# MKRWiFi1010V2_0.net
KiCad netlist of a schematic drawn in EAGLE
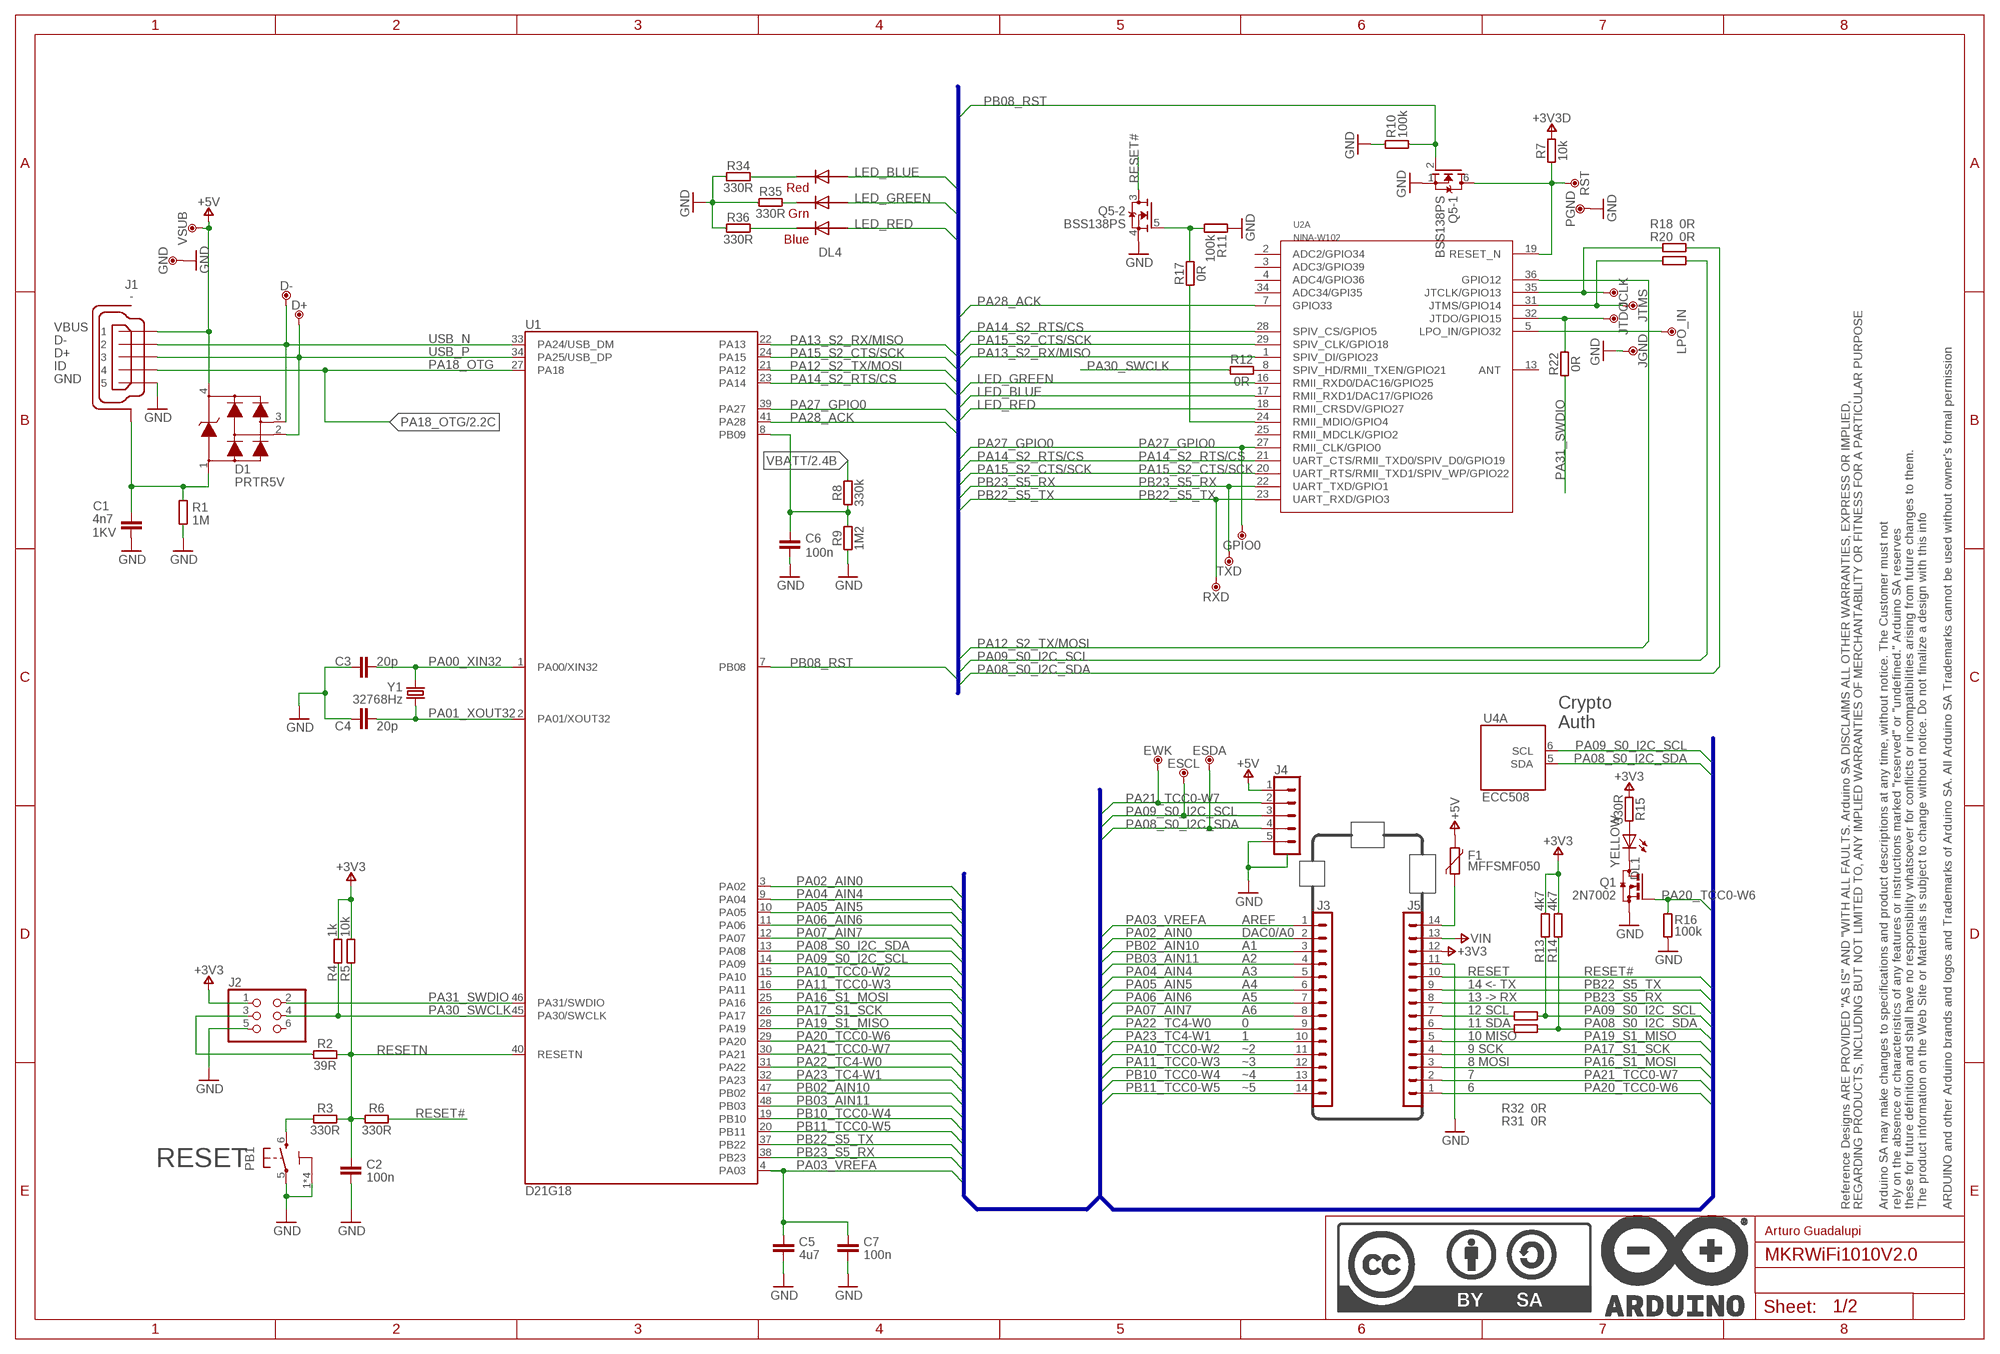
[diagram p0: schematic, sheet 1]
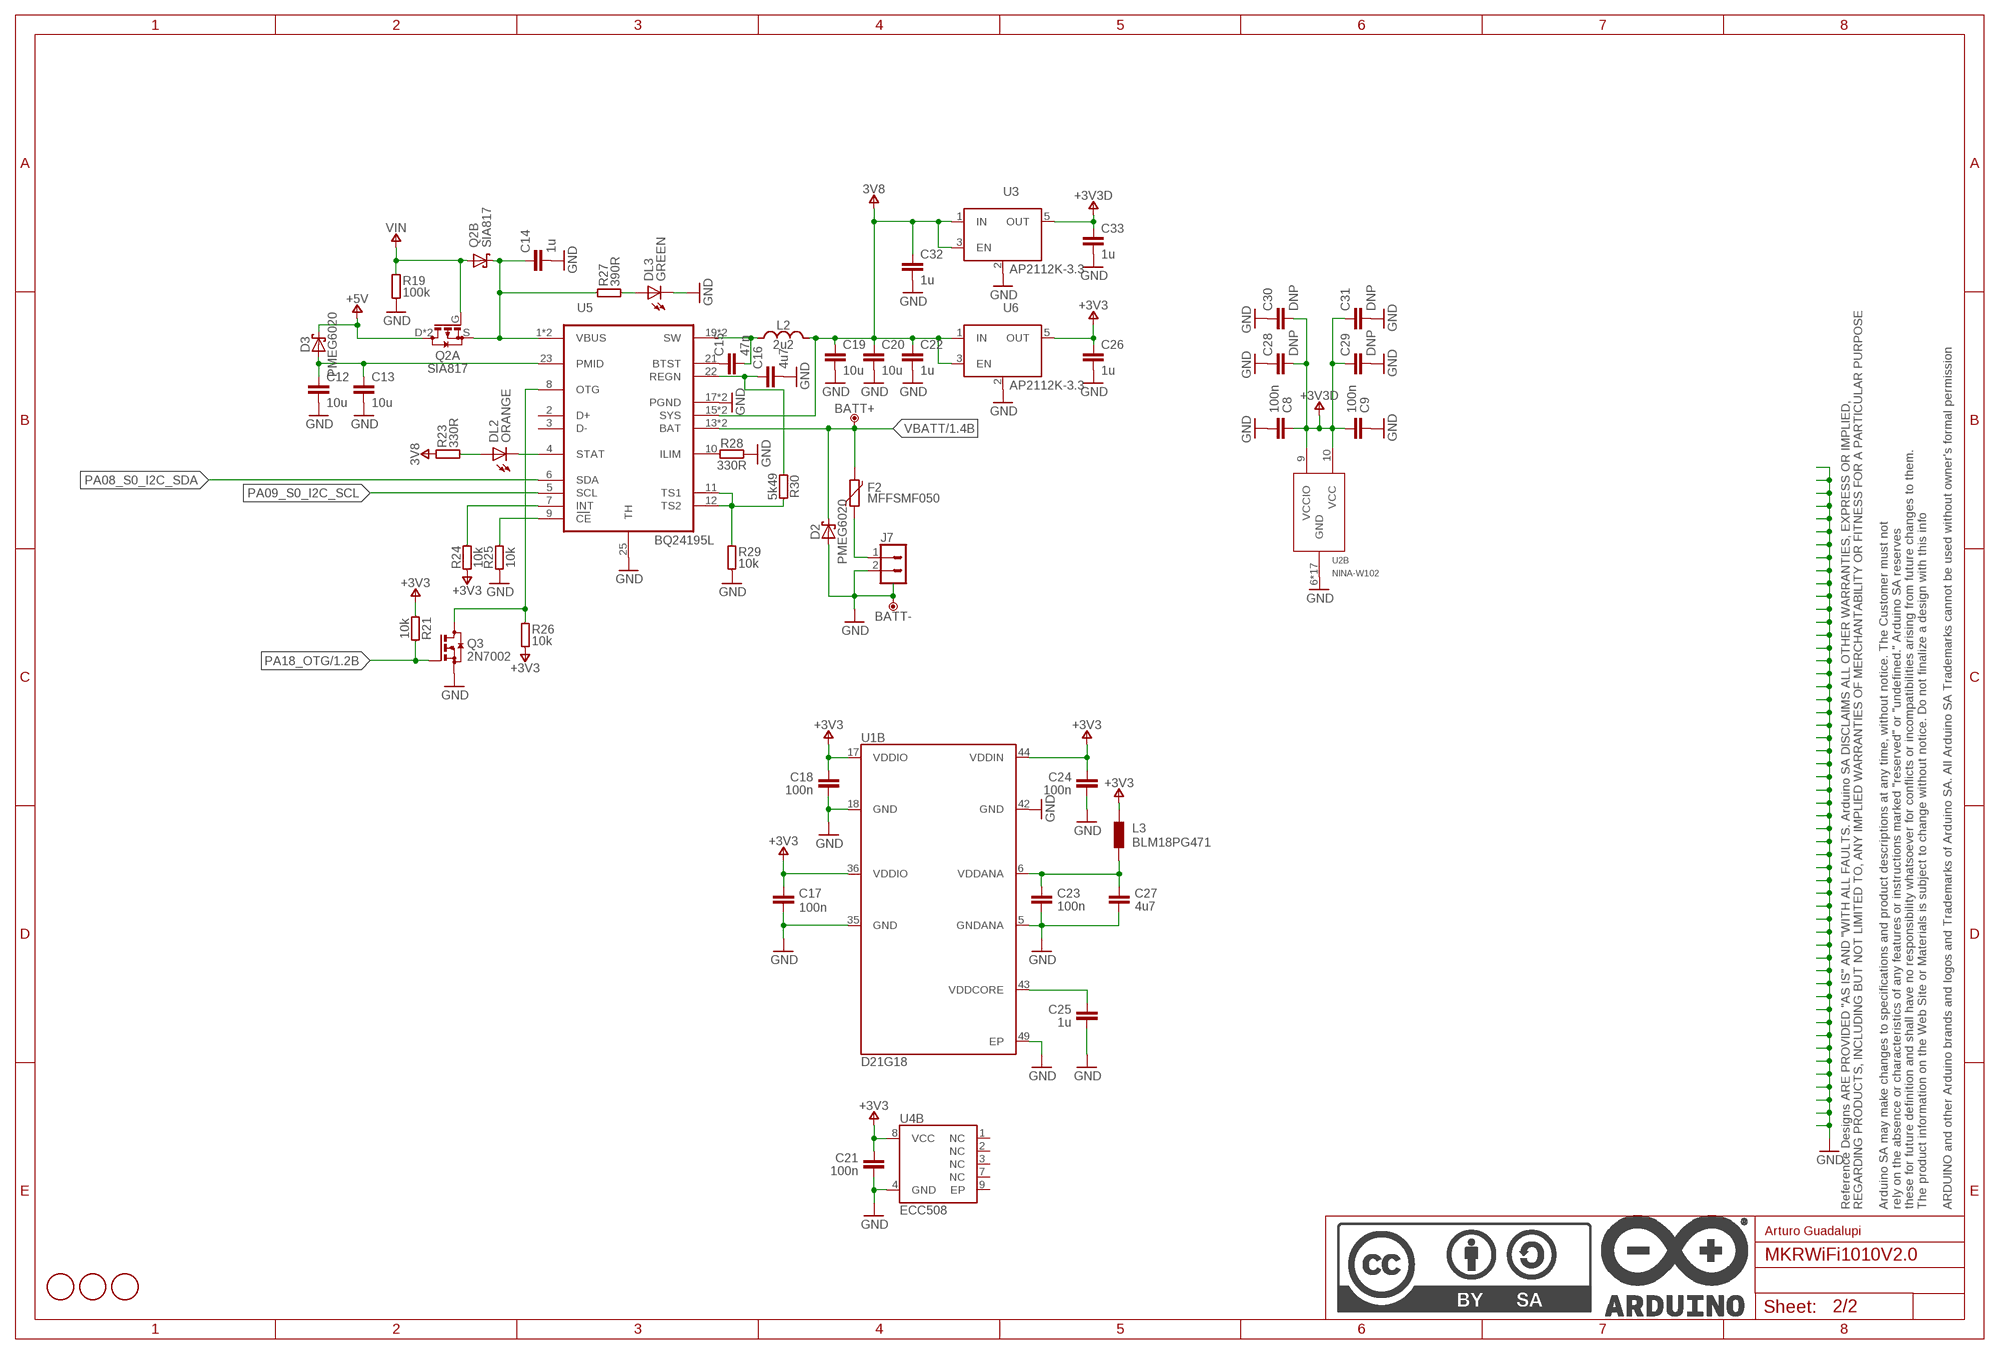
[diagram p1: schematic, sheet 2]

(export (version "E")
  (design (tool "Eeschema 10.0.6"))
  (components
    (comp (ref "C1")
      (value "4n7")
      (footprint "eagle-import:0805-R2013X50N")
      (fields (field (name "MANUFACTURER") "Kemet") (field (name "VOLTAGE") "1KV"))
      (libsource (lib "eagle-import") (part "C-08054.7NF"))
    )
    (comp (ref "C2")
      (value "100n")
      (footprint "eagle-import:0402-1005X55N")
      (fields (field (name "MANUFACTURER") "TDK"))
      (libsource (lib "eagle-import") (part "C-0402-100NF"))
    )
    (comp (ref "C3")
      (value "20p")
      (footprint "eagle-import:0402-1005X55N")
      (fields (field (name "MANUFACTURER") "Kemet"))
      (libsource (lib "eagle-import") (part "C-0402-20PF"))
    )
    (comp (ref "C4")
      (value "20p")
      (footprint "eagle-import:0402-1005X55N")
      (fields (field (name "MANUFACTURER") "Kemet"))
      (libsource (lib "eagle-import") (part "C-0402-20PF"))
    )
    (comp (ref "C5")
      (value "4u7")
      (footprint "eagle-import:0402-1005X55N")
      (fields (field (name "MANUFACTURER") "Murata"))
      (libsource (lib "eagle-import") (part "C-0402-4.7UF"))
    )
    (comp (ref "C6")
      (value "100n")
      (footprint "eagle-import:0402-1005X55N")
      (fields (field (name "MANUFACTURER") "TDK"))
      (libsource (lib "eagle-import") (part "C-0402-100NF"))
    )
    (comp (ref "C7")
      (value "100n")
      (footprint "eagle-import:0402-1005X55N")
      (fields (field (name "MANUFACTURER") "TDK"))
      (libsource (lib "eagle-import") (part "C-0402-100NF"))
    )
    (comp (ref "D+")
      (value "DNP")
      (footprint "eagle-import:TP-1.00MM")
      (libsource (lib "eagle-import") (part "TPTP-1.00MM"))
    )
    (comp (ref "D-")
      (value "DNP")
      (footprint "eagle-import:TP-1.00MM")
      (libsource (lib "eagle-import") (part "TPTP-1.00MM"))
    )
    (comp (ref "D1")
      (value "PRTR5V")
      (footprint "eagle-import:SOT190P230X110-4N")
      (fields (field (name "MANUFACTURER") "NXP"))
      (libsource (lib "eagle-import") (part "PRTR5V0U2X,215"))
    )
    (comp (ref "DL1")
      (value "YELLOW")
      (footprint "eagle-import:LEDC1608X80N-AK")
      (fields (field (name "MANUFACTURER") "Avago"))
      (libsource (lib "eagle-import") (part "LED-0603-YELLOW"))
    )
    (comp (ref "DL4")
      (value "RGB")
      (footprint "eagle-import:RGBLED")
      (fields (field (name "MANUFACTURER") "OSRAM Opto Semiconductors Inc."))
      (libsource (lib "eagle-import") (part "RGBLED5050"))
    )
    (comp (ref "ESCL")
      (value "DNP")
      (footprint "eagle-import:TP-1.00MM")
      (libsource (lib "eagle-import") (part "TPTP-1.00MM"))
    )
    (comp (ref "ESDA")
      (value "DNP")
      (footprint "eagle-import:TP-1.00MM")
      (libsource (lib "eagle-import") (part "TPTP-1.00MM"))
    )
    (comp (ref "EWK")
      (value "DNP")
      (footprint "eagle-import:TP-1.00MM")
      (libsource (lib "eagle-import") (part "TPTP-1.00MM"))
    )
    (comp (ref "F1")
      (value "MFFSMF050")
      (footprint "eagle-import:0603-1608X90N")
      (fields (field (name "MANUFACTURER") "Bourns Inc "))
      (libsource (lib "eagle-import") (part "PTC"))
    )
    (comp (ref "FRAME1")
      (value "DNP")
      (footprint "eagle-import:FRAME")
      (libsource (lib "eagle-import") (part "A3-FRAME"))
    )
    (comp (ref "GND")
      (value "DNP")
      (footprint "eagle-import:TP-1.00MM")
      (libsource (lib "eagle-import") (part "TPTP-1.00MM"))
    )
    (comp (ref "GPIO0")
      (value "DNP")
      (footprint "eagle-import:TP-0.8MM")
      (libsource (lib "eagle-import") (part "TPTP-0.8MM"))
    )
    (comp (ref "J1")
      (value "-")
      (footprint "eagle-import:ZX62-AB-5PA")
      (fields (field (name "MANUFACTURER") "Hirose"))
      (libsource (lib "eagle-import") (part "USB-MICRO"))
    )
    (comp (ref "J2")
      (value "DNP")
      (footprint "eagle-import:2X3_SMT")
      (libsource (lib "eagle-import") (part "PINHD-2X03SMD-NH-DNP"))
    )
    (comp (ref "J3")
      (value "-")
      (footprint "eagle-import:1X14_SMD_TH")
      (fields (field (name "MANUFACTURER") "ELDECO"))
      (libsource (lib "eagle-import") (part "PINHD-1X14-SMTH-SMD-MALE/FEMALE"))
    )
    (comp (ref "J4")
      (value "-")
      (footprint "eagle-import:SM05B-SRSS-TB")
      (fields (field (name "MANUFACTURER") "JST"))
      (libsource (lib "eagle-import") (part "SM05B-SRSS-TB"))
    )
    (comp (ref "J5")
      (value "-")
      (footprint "eagle-import:1X14_SMD_TH")
      (fields (field (name "MANUFACTURER") "ELDECO"))
      (libsource (lib "eagle-import") (part "PINHD-1X14-SMTH-SMD-MALE/FEMALE"))
    )
    (comp (ref "JCLK")
      (value "DNP")
      (footprint "eagle-import:TP-0.8MM")
      (libsource (lib "eagle-import") (part "TPTP-0.8MM"))
    )
    (comp (ref "JGND")
      (value "DNP")
      (footprint "eagle-import:TP-0.8MM")
      (libsource (lib "eagle-import") (part "TPTP-0.8MM"))
    )
    (comp (ref "JTDO")
      (value "DNP")
      (footprint "eagle-import:TP-0.8MM")
      (libsource (lib "eagle-import") (part "TPTP-0.8MM"))
    )
    (comp (ref "JTMS")
      (value "DNP")
      (footprint "eagle-import:TP-0.8MM")
      (libsource (lib "eagle-import") (part "TPTP-0.8MM"))
    )
    (comp (ref "LPO_IN")
      (value "DNP")
      (footprint "eagle-import:TP-1.27MM")
      (libsource (lib "eagle-import") (part "TPTP-1.27MM"))
    )
    (comp (ref "PB1")
      (value "PTS820")
      (footprint "eagle-import:C&K_PTS820_NO_HOLES")
      (fields (field (name "MANUFACTURER") "C&K"))
      (libsource (lib "eagle-import") (part "TACTILE1PTS820-NH"))
    )
    (comp (ref "PGND")
      (value "DNP")
      (footprint "eagle-import:TP-0.8MM")
      (libsource (lib "eagle-import") (part "TPTP-0.8MM"))
    )
    (comp (ref "Q1")
      (value "2N7002")
      (footprint "eagle-import:SOTFL50P160X78-3")
      (fields (field (name "MANUFACTURER") "Diodes Incorporated"))
      (libsource (lib "eagle-import") (part "2N7002T-SOT523"))
    )
    (comp (ref "Q5")
      (value "BSS138PS")
      (footprint "eagle-import:SOT363")
      (fields (field (name "MANUFACTURER") "NXP"))
      (libsource (lib "eagle-import") (part "BSS138PS"))
    )
    (comp (ref "R1")
      (value "1M")
      (footprint "eagle-import:0402-1005X55N")
      (fields (field (name "MANUFACTURER") "Yageo"))
      (libsource (lib "eagle-import") (part "R-0402-1M"))
    )
    (comp (ref "R2")
      (value "39R")
      (footprint "eagle-import:0402-1005X55N")
      (fields (field (name "MANUFACTURER") "Yageo "))
      (libsource (lib "eagle-import") (part "R-0402-39R"))
    )
    (comp (ref "R3")
      (value "330R")
      (footprint "eagle-import:0402-1005X55N")
      (fields (field (name "MANUFACTURER") "Yageo "))
      (libsource (lib "eagle-import") (part "R-0402-330R"))
    )
    (comp (ref "R4")
      (value "1k")
      (footprint "eagle-import:0402-1005X55N")
      (fields (field (name "MANUFACTURER") "Yageo"))
      (libsource (lib "eagle-import") (part "R-0402-1K"))
    )
    (comp (ref "R5")
      (value "10k")
      (footprint "eagle-import:0402-1005X55N")
      (fields (field (name "MANUFACTURER") "Yageo"))
      (libsource (lib "eagle-import") (part "R-0402-10K"))
    )
    (comp (ref "R6")
      (value "330R")
      (footprint "eagle-import:0402-1005X55N")
      (fields (field (name "MANUFACTURER") "Yageo "))
      (libsource (lib "eagle-import") (part "R-0402-330R"))
    )
    (comp (ref "R7")
      (value "10k")
      (footprint "eagle-import:0402-1005X55N")
      (fields (field (name "MANUFACTURER") "Yageo"))
      (libsource (lib "eagle-import") (part "R-0402-10K"))
    )
    (comp (ref "R8")
      (value "330k")
      (footprint "eagle-import:0402-1005X55N")
      (fields (field (name "MANUFACTURER") "Yageo"))
      (libsource (lib "eagle-import") (part "R-0402-330K"))
    )
    (comp (ref "R9")
      (value "1M2")
      (footprint "eagle-import:0402-1005X55N")
      (fields (field (name "MANUFACTURER") "Yageo"))
      (libsource (lib "eagle-import") (part "R-0402-1M2"))
    )
    (comp (ref "R10")
      (value "100k")
      (footprint "eagle-import:0402-1005X55N")
      (fields (field (name "MANUFACTURER") "Yageo "))
      (libsource (lib "eagle-import") (part "R-0402-100K"))
    )
    (comp (ref "R11")
      (value "100k")
      (footprint "eagle-import:0402-1005X55N")
      (fields (field (name "MANUFACTURER") "Yageo "))
      (libsource (lib "eagle-import") (part "R-0402-100K"))
    )
    (comp (ref "R12")
      (value "0R")
      (footprint "eagle-import:0402-1005X55N")
      (fields (field (name "MANUFACTURER") "Yageo"))
      (libsource (lib "eagle-import") (part "R-0402-0R"))
    )
    (comp (ref "R13")
      (value "4k7")
      (footprint "eagle-import:0402-1005X55N")
      (fields (field (name "MANUFACTURER") "Yageo "))
      (libsource (lib "eagle-import") (part "R-0402-4K7"))
    )
    (comp (ref "R14")
      (value "4k7")
      (footprint "eagle-import:0402-1005X55N")
      (fields (field (name "MANUFACTURER") "Yageo "))
      (libsource (lib "eagle-import") (part "R-0402-4K7"))
    )
    (comp (ref "R15")
      (value "330R")
      (footprint "eagle-import:0402-1005X55N")
      (fields (field (name "MANUFACTURER") "Yageo "))
      (libsource (lib "eagle-import") (part "R-0402-330R"))
    )
    (comp (ref "R16")
      (value "100k")
      (footprint "eagle-import:0402-1005X55N")
      (fields (field (name "MANUFACTURER") "Yageo "))
      (libsource (lib "eagle-import") (part "R-0402-100K"))
    )
    (comp (ref "R17")
      (value "0R")
      (footprint "eagle-import:0402-1005X55N")
      (fields (field (name "MANUFACTURER") "Yageo"))
      (libsource (lib "eagle-import") (part "R-0402-0R"))
    )
    (comp (ref "R18")
      (value "0R")
      (footprint "eagle-import:0402-1005X55N")
      (fields (field (name "MANUFACTURER") "Yageo"))
      (libsource (lib "eagle-import") (part "R-0402-0R"))
    )
    (comp (ref "R20")
      (value "0R")
      (footprint "eagle-import:0402-1005X55N")
      (fields (field (name "MANUFACTURER") "Yageo"))
      (libsource (lib "eagle-import") (part "R-0402-0R"))
    )
    (comp (ref "R22")
      (value "0R")
      (footprint "eagle-import:0402-1005X55N")
      (fields (field (name "MANUFACTURER") "Yageo"))
      (libsource (lib "eagle-import") (part "R-0402-0R"))
    )
    (comp (ref "R31")
      (value "0R")
      (footprint "eagle-import:0402-1005X55N")
      (fields (field (name "MANUFACTURER") "Yageo"))
      (libsource (lib "eagle-import") (part "R-0402-0R"))
    )
    (comp (ref "R32")
      (value "0R")
      (footprint "eagle-import:0402-1005X55N")
      (fields (field (name "MANUFACTURER") "Yageo"))
      (libsource (lib "eagle-import") (part "R-0402-0R"))
    )
    (comp (ref "R34")
      (value "330R")
      (footprint "eagle-import:0402-1005X55N")
      (fields (field (name "MANUFACTURER") "Yageo "))
      (libsource (lib "eagle-import") (part "R-0402-330R"))
    )
    (comp (ref "R35")
      (value "330R")
      (footprint "eagle-import:0402-1005X55N")
      (fields (field (name "MANUFACTURER") "Yageo "))
      (libsource (lib "eagle-import") (part "R-0402-330R"))
    )
    (comp (ref "R36")
      (value "330R")
      (footprint "eagle-import:0402-1005X55N")
      (fields (field (name "MANUFACTURER") "Yageo "))
      (libsource (lib "eagle-import") (part "R-0402-330R"))
    )
    (comp (ref "RST")
      (value "DNP")
      (footprint "eagle-import:TP-0.8MM")
      (libsource (lib "eagle-import") (part "TPTP-0.8MM"))
    )
    (comp (ref "RXD")
      (value "DNP")
      (footprint "eagle-import:TP-0.8MM")
      (libsource (lib "eagle-import") (part "TPTP-0.8MM"))
    )
    (comp (ref "TXD")
      (value "DNP")
      (footprint "eagle-import:TP-0.8MM")
      (libsource (lib "eagle-import") (part "TPTP-0.8MM"))
    )
    (comp (ref "U1")
      (value "D21G18")
      (footprint "eagle-import:QFN50P700X700X90-49XN-EPSQ515")
      (fields (field (name "MANUFACTURER") "Atmel"))
      (libsource (lib "eagle-import") (part "ATSAMD21G18A-48QFN"))
    )
    (comp (ref "U2")
      (value "NINA-W102")
      (footprint "eagle-import:NINA-W1X")
      (fields (field (name "MANUFACTURER") "Ublocks"))
      (libsource (lib "eagle-import") (part "NINA-W1X-102"))
    )
    (comp (ref "U4")
      (value "ECC508")
      (footprint "eagle-import:SON50P300X200X60-9N-EP160X140")
      (fields (field (name "MANUFACTURER") "Atmel"))
      (libsource (lib "eagle-import") (part "ATECC508A-MAHDA-T8-UDFN"))
    )
    (comp (ref "VSUB")
      (value "DNP")
      (footprint "eagle-import:TP-1.00MM")
      (libsource (lib "eagle-import") (part "TPTP-1.00MM"))
    )
    (comp (ref "Y1")
      (value "32768Hz")
      (footprint "eagle-import:ABS07")
      (fields (field (name "MANUFACTURER") "Abracon LLC"))
      (libsource (lib "eagle-import") (part "32.768KHZ"))
    )
    (comp (ref "BATT+")
      (value "DNP")
      (footprint "eagle-import:TP-1.00MM")
      (libsource (lib "eagle-import") (part "TPTP-1.00MM"))
    )
    (comp (ref "BATT-")
      (value "DNP")
      (footprint "eagle-import:TP-1.00MM")
      (libsource (lib "eagle-import") (part "TPTP-1.00MM"))
    )
    (comp (ref "C8")
      (value "100n")
      (footprint "eagle-import:0402-1005X55N")
      (fields (field (name "MANUFACTURER") "TDK"))
      (libsource (lib "eagle-import") (part "C-0402-100NF"))
    )
    (comp (ref "C9")
      (value "100n")
      (footprint "eagle-import:0402-1005X55N")
      (fields (field (name "MANUFACTURER") "TDK"))
      (libsource (lib "eagle-import") (part "C-0402-100NF"))
    )
    (comp (ref "C12")
      (value "10u")
      (footprint "eagle-import:0603-1608X90N")
      (fields (field (name "MANUFACTURER") "Murata"))
      (libsource (lib "eagle-import") (part "C-0603-10UF"))
    )
    (comp (ref "C13")
      (value "10u")
      (footprint "eagle-import:0603-1608X90N")
      (fields (field (name "MANUFACTURER") "Murata"))
      (libsource (lib "eagle-import") (part "C-0603-10UF"))
    )
    (comp (ref "C14")
      (value "1u")
      (footprint "eagle-import:0402-1005X55N")
      (fields (field (name "MANUFACTURER") "Murata"))
      (libsource (lib "eagle-import") (part "C-0402-1UF"))
    )
    (comp (ref "C15")
      (value "47n")
      (footprint "eagle-import:0402-1005X55N")
      (fields (field (name "MANUFACTURER") "Murata"))
      (libsource (lib "eagle-import") (part "C-0402-47N"))
    )
    (comp (ref "C16")
      (value "4u7")
      (footprint "eagle-import:0402-1005X55N")
      (fields (field (name "MANUFACTURER") "Murata"))
      (libsource (lib "eagle-import") (part "C-0402-4.7UF"))
    )
    (comp (ref "C17")
      (value "100n")
      (footprint "eagle-import:0402-1005X55N")
      (fields (field (name "MANUFACTURER") "TDK"))
      (libsource (lib "eagle-import") (part "C-0402-100NF"))
    )
    (comp (ref "C18")
      (value "100n")
      (footprint "eagle-import:0402-1005X55N")
      (fields (field (name "MANUFACTURER") "TDK"))
      (libsource (lib "eagle-import") (part "C-0402-100NF"))
    )
    (comp (ref "C19")
      (value "10u")
      (footprint "eagle-import:0603-1608X90N")
      (fields (field (name "MANUFACTURER") "Murata"))
      (libsource (lib "eagle-import") (part "C-0603-10UF"))
    )
    (comp (ref "C20")
      (value "10u")
      (footprint "eagle-import:0603-1608X90N")
      (fields (field (name "MANUFACTURER") "Murata"))
      (libsource (lib "eagle-import") (part "C-0603-10UF"))
    )
    (comp (ref "C21")
      (value "100n")
      (footprint "eagle-import:0402-1005X55N")
      (fields (field (name "MANUFACTURER") "TDK"))
      (libsource (lib "eagle-import") (part "C-0402-100NF"))
    )
    (comp (ref "C22")
      (value "1u")
      (footprint "eagle-import:0402-1005X55N")
      (fields (field (name "MANUFACTURER") "Murata"))
      (libsource (lib "eagle-import") (part "C-0402-1UF"))
    )
    (comp (ref "C23")
      (value "100n")
      (footprint "eagle-import:0402-1005X55N")
      (fields (field (name "MANUFACTURER") "TDK"))
      (libsource (lib "eagle-import") (part "C-0402-100NF"))
    )
    (comp (ref "C24")
      (value "100n")
      (footprint "eagle-import:0402-1005X55N")
      (fields (field (name "MANUFACTURER") "TDK"))
      (libsource (lib "eagle-import") (part "C-0402-100NF"))
    )
    (comp (ref "C25")
      (value "1u")
      (footprint "eagle-import:0402-1005X55N")
      (fields (field (name "MANUFACTURER") "Murata"))
      (libsource (lib "eagle-import") (part "C-0402-1UF"))
    )
    (comp (ref "C26")
      (value "1u")
      (footprint "eagle-import:0402-1005X55N")
      (fields (field (name "MANUFACTURER") "Murata"))
      (libsource (lib "eagle-import") (part "C-0402-1UF"))
    )
    (comp (ref "C27")
      (value "4u7")
      (footprint "eagle-import:0603-1608X90N")
      (fields (field (name "MANUFACTURER") "Murata"))
      (libsource (lib "eagle-import") (part "C-0603-4.7UF"))
    )
    (comp (ref "C28")
      (value "DNP")
      (footprint "eagle-import:0402-1005X55N")
      (libsource (lib "eagle-import") (part "C-0402DNP"))
    )
    (comp (ref "C29")
      (value "DNP")
      (footprint "eagle-import:0402-1005X55N")
      (libsource (lib "eagle-import") (part "C-0402DNP"))
    )
    (comp (ref "C30")
      (value "DNP")
      (footprint "eagle-import:0603-1608X90N")
      (libsource (lib "eagle-import") (part "C-0603-DNP"))
    )
    (comp (ref "C31")
      (value "DNP")
      (footprint "eagle-import:0603-1608X90N")
      (libsource (lib "eagle-import") (part "C-0603-DNP"))
    )
    (comp (ref "C32")
      (value "1u")
      (footprint "eagle-import:0402-1005X55N")
      (fields (field (name "MANUFACTURER") "Murata"))
      (libsource (lib "eagle-import") (part "C-0402-1UF"))
    )
    (comp (ref "C33")
      (value "1u")
      (footprint "eagle-import:0402-1005X55N")
      (fields (field (name "MANUFACTURER") "Murata"))
      (libsource (lib "eagle-import") (part "C-0402-1UF"))
    )
    (comp (ref "D2")
      (value "PMEG6020")
      (footprint "eagle-import:SODFL3517X110N")
      (fields (field (name "MANUFACTURER") "NXP"))
      (libsource (lib "eagle-import") (part "PMEG6020AELRX"))
    )
    (comp (ref "D3")
      (value "PMEG6020")
      (footprint "eagle-import:SODFL3517X110N")
      (fields (field (name "MANUFACTURER") "NXP"))
      (libsource (lib "eagle-import") (part "PMEG6020AELRX"))
    )
    (comp (ref "DL2")
      (value "ORANGE")
      (footprint "eagle-import:LEDC1608X80N-AK")
      (fields (field (name "MANUFACTURER") "Avago "))
      (libsource (lib "eagle-import") (part "LED-0603-ORANGE"))
    )
    (comp (ref "DL3")
      (value "GREEN")
      (footprint "eagle-import:LEDC1608X80N-AK")
      (fields (field (name "MANUFACTURER") "Avago "))
      (libsource (lib "eagle-import") (part "LED-0603-GREEN"))
    )
    (comp (ref "F2")
      (value "MFFSMF050")
      (footprint "eagle-import:0603-1608X90N")
      (fields (field (name "MANUFACTURER") "Bourns Inc "))
      (libsource (lib "eagle-import") (part "PTC"))
    )
    (comp (ref "FD1")
      (value "DNP")
      (footprint "eagle-import:FD-1-1.5")
      (libsource (lib "eagle-import") (part "FIDUCIAL-1.5MM"))
    )
    (comp (ref "FD2")
      (value "DNP")
      (footprint "eagle-import:FD-1-1.5")
      (libsource (lib "eagle-import") (part "FIDUCIAL-1.5MM"))
    )
    (comp (ref "FD3")
      (value "DNP")
      (footprint "eagle-import:FD-1-1.5")
      (libsource (lib "eagle-import") (part "FIDUCIAL-1.5MM"))
    )
    (comp (ref "FRAME2")
      (value "DNP")
      (footprint "eagle-import:FRAME")
      (libsource (lib "eagle-import") (part "A3-FRAME"))
    )
    (comp (ref "J7")
      (value "-")
      (footprint "eagle-import:JST-S2B-PH-SM4-TB")
      (fields (field (name "MANUFACTURER") "JST "))
      (libsource (lib "eagle-import") (part "BATTERY"))
    )
    (comp (ref "L2")
      (value "2u2")
      (footprint "eagle-import:SRP4020")
      (fields (field (name "MANUFACTURER") "Bourns"))
      (libsource (lib "eagle-import") (part "LSRP"))
    )
    (comp (ref "L3")
      (value "BLM18PG471")
      (footprint "eagle-import:0603-1608X90N")
      (fields (field (name "MANUFACTURER") "Murata"))
      (libsource (lib "eagle-import") (part "FERRITE0603-470R"))
    )
    (comp (ref "Q2")
      (value "SIA817")
      (footprint "eagle-import:SON65P205X205X75-8N-MWSD")
      (fields (field (name "MANUFACTURER") "Vishay "))
      (libsource (lib "eagle-import") (part "SIA817EDJ"))
    )
    (comp (ref "Q3")
      (value "2N7002")
      (footprint "eagle-import:SOTFL50P160X78-3")
      (fields (field (name "MANUFACTURER") "Diodes Incorporated"))
      (libsource (lib "eagle-import") (part "2N7002T-SOT523"))
    )
    (comp (ref "R19")
      (value "100k")
      (footprint "eagle-import:0402-1005X55N")
      (fields (field (name "MANUFACTURER") "Yageo "))
      (libsource (lib "eagle-import") (part "R-0402-100K"))
    )
    (comp (ref "R21")
      (value "10k")
      (footprint "eagle-import:0402-1005X55N")
      (fields (field (name "MANUFACTURER") "Yageo"))
      (libsource (lib "eagle-import") (part "R-0402-10K"))
    )
    (comp (ref "R23")
      (value "330R")
      (footprint "eagle-import:0402-1005X55N")
      (fields (field (name "MANUFACTURER") "Yageo "))
      (libsource (lib "eagle-import") (part "R-0402-330R"))
    )
    (comp (ref "R24")
      (value "10k")
      (footprint "eagle-import:0402-1005X55N")
      (fields (field (name "MANUFACTURER") "Yageo"))
      (libsource (lib "eagle-import") (part "R-0402-10K"))
    )
    (comp (ref "R25")
      (value "10k")
      (footprint "eagle-import:0402-1005X55N")
      (fields (field (name "MANUFACTURER") "Yageo"))
      (libsource (lib "eagle-import") (part "R-0402-10K"))
    )
    (comp (ref "R26")
      (value "10k")
      (footprint "eagle-import:0402-1005X55N")
      (fields (field (name "MANUFACTURER") "Yageo"))
      (libsource (lib "eagle-import") (part "R-0402-10K"))
    )
    (comp (ref "R27")
      (value "390R")
      (footprint "eagle-import:0402-1005X55N")
      (fields (field (name "MANUFACTURER") "Yageo"))
      (libsource (lib "eagle-import") (part "R-0402-390R"))
    )
    (comp (ref "R28")
      (value "330R")
      (footprint "eagle-import:0402-1005X55N")
      (fields (field (name "MANUFACTURER") "Yageo "))
      (libsource (lib "eagle-import") (part "R-0402-330R"))
    )
    (comp (ref "R29")
      (value "10k")
      (footprint "eagle-import:0402-1005X55N")
      (fields (field (name "MANUFACTURER") "Yageo"))
      (libsource (lib "eagle-import") (part "R-0402-10K"))
    )
    (comp (ref "R30")
      (value "5k49")
      (footprint "eagle-import:0402-1005X55N")
      (fields (field (name "MANUFACTURER") "Yageo"))
      (libsource (lib "eagle-import") (part "R-0402-5K49"))
    )
    (comp (ref "U3")
      (value "AP2112K-3.3")
      (footprint "eagle-import:SOT25")
      (fields (field (name "MANUFACTURER") "Diodes Inc"))
      (libsource (lib "eagle-import") (part "AP2112K-3.3"))
    )
    (comp (ref "U5")
      (value "BQ24195L")
      (footprint "eagle-import:QFN24")
      (fields (field (name "MANUFACTURER") " Texas Instruments "))
      (libsource (lib "eagle-import") (part "BQ24195QFN-24"))
    )
    (comp (ref "U6")
      (value "AP2112K-3.3")
      (footprint "eagle-import:SOT25")
      (fields (field (name "MANUFACTURER") "Diodes Inc"))
      (libsource (lib "eagle-import") (part "AP2112K-3.3"))
    )
  )
  (nets
    (net (code "1") (name "+3V3") (class "Default")
      (node (ref "C17") (pin "1") (pinfunction "1_1") (pintype "passive"))
      (node (ref "C18") (pin "1") (pinfunction "1_1") (pintype "passive"))
      (node (ref "C21") (pin "1") (pinfunction "1_1") (pintype "passive"))
      (node (ref "C24") (pin "1") (pinfunction "1_1") (pintype "passive"))
      (node (ref "C26") (pin "1") (pinfunction "1_1") (pintype "passive"))
      (node (ref "J2") (pin "1") (pinfunction "1_1") (pintype "passive"))
      (node (ref "J5") (pin "12") (pinfunction "12_12") (pintype "passive"))
      (node (ref "L3") (pin "1") (pinfunction "1_1") (pintype "passive"))
      (node (ref "R13") (pin "2") (pinfunction "2_2") (pintype "passive"))
      (node (ref "R14") (pin "2") (pinfunction "2_2") (pintype "passive"))
      (node (ref "R15") (pin "1") (pinfunction "1_1") (pintype "passive"))
      (node (ref "R21") (pin "1") (pinfunction "1_1") (pintype "passive"))
      (node (ref "R24") (pin "1") (pinfunction "1_1") (pintype "passive"))
      (node (ref "R26") (pin "1") (pinfunction "1_1") (pintype "passive"))
      (node (ref "R4") (pin "2") (pinfunction "2_2") (pintype "passive"))
      (node (ref "R5") (pin "2") (pinfunction "2_2") (pintype "passive"))
      (node (ref "U1") (pin "17") (pinfunction "VDDIO_17") (pintype "power_in"))
      (node (ref "U1") (pin "36") (pinfunction "VDDIO_36") (pintype "power_in"))
      (node (ref "U1") (pin "44") (pinfunction "VDDIN_44") (pintype "power_in"))
      (node (ref "U4") (pin "8") (pinfunction "VCC_8") (pintype "power_in"))
      (node (ref "U6") (pin "5") (pinfunction "OUT_5") (pintype "power_in"))
    )
    (net (code "2") (name "+3V3D") (class "Default")
      (node (ref "C28") (pin "2") (pinfunction "2_2") (pintype "passive"))
      (node (ref "C29") (pin "1") (pinfunction "1_1") (pintype "passive"))
      (node (ref "C30") (pin "2") (pinfunction "2_2") (pintype "passive"))
      (node (ref "C31") (pin "1") (pinfunction "1_1") (pintype "passive"))
      (node (ref "C33") (pin "1") (pinfunction "1_1") (pintype "passive"))
      (node (ref "C8") (pin "1") (pinfunction "1_1") (pintype "passive"))
      (node (ref "C9") (pin "2") (pinfunction "2_2") (pintype "passive"))
      (node (ref "R7") (pin "2") (pinfunction "2_2") (pintype "passive"))
      (node (ref "U2") (pin "10") (pinfunction "VCC_10") (pintype "bidirectional"))
      (node (ref "U2") (pin "9") (pinfunction "VCCIO_9") (pintype "bidirectional"))
      (node (ref "U3") (pin "5") (pinfunction "OUT_5") (pintype "power_in"))
    )
    (net (code "3") (name "+3V8") (class "Default")
      (node (ref "C19") (pin "1") (pinfunction "1_1") (pintype "passive"))
      (node (ref "C20") (pin "1") (pinfunction "1_1") (pintype "passive"))
      (node (ref "C22") (pin "1") (pinfunction "1_1") (pintype "passive"))
      (node (ref "C32") (pin "1") (pinfunction "1_1") (pintype "passive"))
      (node (ref "L2") (pin "2") (pinfunction "2_2") (pintype "passive"))
      (node (ref "R23") (pin "2") (pinfunction "2_2") (pintype "passive"))
      (node (ref "U3") (pin "1") (pinfunction "IN_1") (pintype "power_in"))
      (node (ref "U3") (pin "3") (pinfunction "EN_3") (pintype "input"))
      (node (ref "U5") (pin "15") (pinfunction "SYS_15") (pintype "bidirectional"))
      (node (ref "U5") (pin "16") (pinfunction "SYS_16") (pintype "bidirectional"))
      (node (ref "U6") (pin "1") (pinfunction "IN_1") (pintype "power_in"))
      (node (ref "U6") (pin "3") (pinfunction "EN_3") (pintype "input"))
    )
    (net (code "4") (name "+5V") (class "Default")
      (node (ref "D1") (pin "4") (pinfunction "4_4") (pintype "passive"))
      (node (ref "D3") (pin "C") (pinfunction "C_C") (pintype "passive"))
      (node (ref "F1") (pin "2") (pinfunction "2_2") (pintype "passive"))
      (node (ref "J1") (pin "1") (pinfunction "1_1") (pintype "passive"))
      (node (ref "J4") (pin "1") (pinfunction "1_1") (pintype "passive"))
      (node (ref "Q2") (pin "D") (pinfunction "D_D") (pintype "passive"))
      (node (ref "Q2") (pin "D2") (pinfunction "D_D2") (pintype "passive"))
      (node (ref "VSUB") (pin "X") (pinfunction "P$1_X") (pintype "passive"))
    )
    (net (code "5") (name "GND") (class "Default")
      (node (ref "BATT-") (pin "X") (pinfunction "P$1_X") (pintype "passive"))
      (node (ref "C1") (pin "2") (pinfunction "2_2") (pintype "passive"))
      (node (ref "C12") (pin "2") (pinfunction "2_2") (pintype "passive"))
      (node (ref "C13") (pin "2") (pinfunction "2_2") (pintype "passive"))
      (node (ref "C14") (pin "2") (pinfunction "2_2") (pintype "passive"))
      (node (ref "C16") (pin "2") (pinfunction "2_2") (pintype "passive"))
      (node (ref "C17") (pin "2") (pinfunction "2_2") (pintype "passive"))
      (node (ref "C18") (pin "2") (pinfunction "2_2") (pintype "passive"))
      (node (ref "C19") (pin "2") (pinfunction "2_2") (pintype "passive"))
      (node (ref "C2") (pin "2") (pinfunction "2_2") (pintype "passive"))
      (node (ref "C20") (pin "2") (pinfunction "2_2") (pintype "passive"))
      (node (ref "C21") (pin "2") (pinfunction "2_2") (pintype "passive"))
      (node (ref "C22") (pin "2") (pinfunction "2_2") (pintype "passive"))
      (node (ref "C23") (pin "2") (pinfunction "2_2") (pintype "passive"))
      (node (ref "C24") (pin "2") (pinfunction "2_2") (pintype "passive"))
      (node (ref "C25") (pin "2") (pinfunction "2_2") (pintype "passive"))
      (node (ref "C26") (pin "2") (pinfunction "2_2") (pintype "passive"))
      (node (ref "C27") (pin "2") (pinfunction "2_2") (pintype "passive"))
      (node (ref "C28") (pin "1") (pinfunction "1_1") (pintype "passive"))
      (node (ref "C29") (pin "2") (pinfunction "2_2") (pintype "passive"))
      (node (ref "C3") (pin "1") (pinfunction "1_1") (pintype "passive"))
      (node (ref "C30") (pin "1") (pinfunction "1_1") (pintype "passive"))
      (node (ref "C31") (pin "2") (pinfunction "2_2") (pintype "passive"))
      (node (ref "C32") (pin "2") (pinfunction "2_2") (pintype "passive"))
      (node (ref "C33") (pin "2") (pinfunction "2_2") (pintype "passive"))
      (node (ref "C4") (pin "1") (pinfunction "1_1") (pintype "passive"))
      (node (ref "C5") (pin "2") (pinfunction "2_2") (pintype "passive"))
      (node (ref "C6") (pin "2") (pinfunction "2_2") (pintype "passive"))
      (node (ref "C7") (pin "2") (pinfunction "2_2") (pintype "passive"))
      (node (ref "C8") (pin "2") (pinfunction "2_2") (pintype "passive"))
      (node (ref "C9") (pin "1") (pinfunction "1_1") (pintype "passive"))
      (node (ref "D2") (pin "A") (pinfunction "A_A") (pintype "passive"))
      (node (ref "DL3") (pin "C") (pinfunction "C_C") (pintype "passive"))
      (node (ref "GND") (pin "X") (pinfunction "P$1_X") (pintype "passive"))
      (node (ref "J1") (pin "5") (pinfunction "5_5") (pintype "passive"))
      (node (ref "J2") (pin "5") (pinfunction "5_5") (pintype "passive"))
      (node (ref "J4") (pin "5") (pinfunction "5_5") (pintype "passive"))
      (node (ref "J4") (pin "SH1") (pinfunction "SH_SH1") (pintype "passive"))
      (node (ref "J4") (pin "SH2") (pinfunction "SH_SH2") (pintype "passive"))
      (node (ref "J5") (pin "11") (pinfunction "11_11") (pintype "passive"))
      (node (ref "J7") (pin "2") (pinfunction "2_2") (pintype "passive"))
      (node (ref "J7") (pin "3") (pinfunction "SH_3") (pintype "passive"))
      (node (ref "J7") (pin "4") (pinfunction "SH_4") (pintype "passive"))
      (node (ref "JGND") (pin "X") (pinfunction "P$1_X") (pintype "passive"))
      (node (ref "PB1") (pin "1") (pinfunction "3_1") (pintype "power_in"))
      (node (ref "PB1") (pin "2") (pinfunction "3_2") (pintype "power_in"))
      (node (ref "PB1") (pin "3") (pinfunction "3_3") (pintype "power_in"))
      (node (ref "PB1") (pin "4") (pinfunction "3_4") (pintype "power_in"))
      (node (ref "PB1") (pin "5") (pinfunction "1_5") (pintype "passive"))
      (node (ref "PGND") (pin "X") (pinfunction "P$1_X") (pintype "passive"))
      (node (ref "Q1") (pin "S") (pinfunction "S_S") (pintype "passive"))
      (node (ref "Q3") (pin "S") (pinfunction "S_S") (pintype "passive"))
      (node (ref "Q5") (pin "1") (pinfunction "S_1") (pintype "passive"))
      (node (ref "Q5") (pin "4") (pinfunction "S_4") (pintype "passive"))
      (node (ref "R1") (pin "1") (pinfunction "1_1") (pintype "passive"))
      (node (ref "R10") (pin "2") (pinfunction "2_2") (pintype "passive"))
      (node (ref "R11") (pin "2") (pinfunction "2_2") (pintype "passive"))
      (node (ref "R16") (pin "1") (pinfunction "1_1") (pintype "passive"))
      (node (ref "R19") (pin "1") (pinfunction "1_1") (pintype "passive"))
      (node (ref "R25") (pin "1") (pinfunction "1_1") (pintype "passive"))
      (node (ref "R28") (pin "2") (pinfunction "2_2") (pintype "passive"))
      (node (ref "R29") (pin "1") (pinfunction "1_1") (pintype "passive"))
      (node (ref "R34") (pin "1") (pinfunction "1_1") (pintype "passive"))
      (node (ref "R35") (pin "1") (pinfunction "1_1") (pintype "passive"))
      (node (ref "R36") (pin "1") (pinfunction "1_1") (pintype "passive"))
      (node (ref "R9") (pin "1") (pinfunction "1_1") (pintype "passive"))
      (node (ref "U1") (pin "18") (pinfunction "GND_18") (pintype "power_in"))
      (node (ref "U1") (pin "35") (pinfunction "GND_35") (pintype "power_in"))
      (node (ref "U1") (pin "42") (pinfunction "GND_42") (pintype "power_in"))
      (node (ref "U1") (pin "49") (pinfunction "EP_49") (pintype "passive"))
      (node (ref "U1") (pin "5") (pinfunction "GNDANA_5") (pintype "power_in"))
      (node (ref "U2") (pin "12") (pinfunction "GND_12") (pintype "bidirectional"))
      (node (ref "U2") (pin "14") (pinfunction "GND_14") (pintype "bidirectional"))
      (node (ref "U2") (pin "26") (pinfunction "GND_26") (pintype "bidirectional"))
      (node (ref "U2") (pin "30") (pinfunction "GND_30") (pintype "bidirectional"))
      (node (ref "U2") (pin "6") (pinfunction "GND_6") (pintype "bidirectional"))
      (node (ref "U2") (pin "GND@1") (pinfunction "GND_GND@1") (pintype "bidirectional"))
      (node (ref "U2") (pin "GND@10") (pinfunction "GND_GND@10") (pintype "bidirectional"))
      (node (ref "U2") (pin "GND@11") (pinfunction "GND_GND@11") (pintype "bidirectional"))
      (node (ref "U2") (pin "GND@12") (pinfunction "GND_GND@12") (pintype "bidirectional"))
      (node (ref "U2") (pin "GND@2") (pinfunction "GND_GND@2") (pintype "bidirectional"))
      (node (ref "U2") (pin "GND@3") (pinfunction "GND_GND@3") (pintype "bidirectional"))
      (node (ref "U2") (pin "GND@4") (pinfunction "GND_GND@4") (pintype "bidirectional"))
      (node (ref "U2") (pin "GND@5") (pinfunction "GND_GND@5") (pintype "bidirectional"))
      (node (ref "U2") (pin "GND@6") (pinfunction "GND_GND@6") (pintype "bidirectional"))
      (node (ref "U2") (pin "GND@7") (pinfunction "GND_GND@7") (pintype "bidirectional"))
      (node (ref "U2") (pin "GND@8") (pinfunction "GND_GND@8") (pintype "bidirectional"))
      (node (ref "U2") (pin "GND@9") (pinfunction "GND_GND@9") (pintype "bidirectional"))
      (node (ref "U3") (pin "2") (pinfunction "GND/ADJ_2") (pintype "power_in"))
      (node (ref "U4") (pin "4") (pinfunction "GND_4") (pintype "power_in"))
      (node (ref "U5") (pin "17") (pinfunction "PGND_17") (pintype "bidirectional"))
      (node (ref "U5") (pin "18") (pinfunction "PGND_18") (pintype "bidirectional"))
      (node (ref "U5") (pin "25") (pinfunction "TH_25") (pintype "bidirectional"))
      (node (ref "U6") (pin "2") (pinfunction "GND/ADJ_2") (pintype "power_in"))
    )
    (net (code "6") (name "LED_BLUE") (class "Default")
      (node (ref "DL4") (pin "2") (pinfunction "RED_A_2") (pintype "bidirectional"))
      (node (ref "U2") (pin "17") (pinfunction "RMII_RXD1/DAC17/GPIO26_17") (pintype "bidirectional"))
    )
    (net (code "7") (name "LED_GREEN") (class "Default")
      (node (ref "DL4") (pin "1") (pinfunction "GREEN_A_1") (pintype "bidirectional"))
      (node (ref "U2") (pin "16") (pinfunction "RMII_RXD0/DAC16/GPIO25_16") (pintype "bidirectional"))
    )
    (net (code "8") (name "LED_RED") (class "Default")
      (node (ref "DL4") (pin "3") (pinfunction "BLUE_A_3") (pintype "bidirectional"))
      (node (ref "U2") (pin "18") (pinfunction "RMII_CRSDV/GPIO27_18") (pintype "bidirectional"))
    )
    (net (code "9") (name "Net-(C1-Pad1)") (class "Default")
      (node (ref "C1") (pin "1") (pinfunction "1_1") (pintype "passive"))
      (node (ref "D1") (pin "1") (pinfunction "1_1") (pintype "passive"))
      (node (ref "J1") (pin "10") (pinfunction "SH_10") (pintype "passive"))
      (node (ref "J1") (pin "11") (pinfunction "SH_11") (pintype "passive"))
      (node (ref "J1") (pin "6") (pinfunction "SH_6") (pintype "passive"))
      (node (ref "J1") (pin "7") (pinfunction "SH_7") (pintype "passive"))
      (node (ref "J1") (pin "8") (pinfunction "SH_8") (pintype "passive"))
      (node (ref "J1") (pin "9") (pinfunction "SH_9") (pintype "passive"))
      (node (ref "R1") (pin "2") (pinfunction "2_2") (pintype "passive"))
    )
    (net (code "10") (name "Net-(C14-Pad1)") (class "Default")
      (node (ref "C14") (pin "1") (pinfunction "1_1") (pintype "passive"))
      (node (ref "Q2") (pin "K") (pinfunction "C_K") (pintype "passive"))
      (node (ref "Q2") (pin "K2") (pinfunction "C_K2") (pintype "passive"))
      (node (ref "Q2") (pin "S") (pinfunction "S_S") (pintype "passive"))
      (node (ref "R27") (pin "2") (pinfunction "2_2") (pintype "passive"))
      (node (ref "U5") (pin "1") (pinfunction "VBUS_1") (pintype "bidirectional"))
      (node (ref "U5") (pin "24") (pinfunction "VBUS_24") (pintype "bidirectional"))
    )
    (net (code "11") (name "Net-(C15-Pad2)") (class "Default")
      (node (ref "C15") (pin "2") (pinfunction "2_2") (pintype "passive"))
      (node (ref "L2") (pin "1") (pinfunction "1_1") (pintype "passive"))
      (node (ref "U5") (pin "19") (pinfunction "SW_19") (pintype "bidirectional"))
      (node (ref "U5") (pin "20") (pinfunction "SW_20") (pintype "bidirectional"))
    )
    (net (code "12") (name "Net-(DL1-PadA)") (class "Default")
      (node (ref "DL1") (pin "A") (pinfunction "A_A") (pintype "passive"))
      (node (ref "R15") (pin "2") (pinfunction "2_2") (pintype "passive"))
    )
    (net (code "13") (name "Net-(DL1-PadC)") (class "Default")
      (node (ref "DL1") (pin "C") (pinfunction "C_C") (pintype "passive"))
      (node (ref "Q1") (pin "D") (pinfunction "D_D") (pintype "passive"))
    )
    (net (code "14") (name "Net-(DL2-PadA)") (class "Default")
      (node (ref "DL2") (pin "A") (pinfunction "A_A") (pintype "passive"))
      (node (ref "R23") (pin "1") (pinfunction "1_1") (pintype "passive"))
    )
    (net (code "15") (name "Net-(DL3-PadA)") (class "Default")
      (node (ref "DL3") (pin "A") (pinfunction "A_A") (pintype "passive"))
      (node (ref "R27") (pin "1") (pinfunction "1_1") (pintype "passive"))
    )
    (net (code "16") (name "Net-(DL4-BLUE_C)") (class "Default")
      (node (ref "DL4") (pin "4") (pinfunction "BLUE_C_4") (pintype "bidirectional"))
      (node (ref "R36") (pin "2") (pinfunction "2_2") (pintype "passive"))
    )
    (net (code "17") (name "Net-(DL4-GREEN_C)") (class "Default")
      (node (ref "DL4") (pin "6") (pinfunction "GREEN_C_6") (pintype "bidirectional"))
      (node (ref "R35") (pin "2") (pinfunction "2_2") (pintype "passive"))
    )
    (net (code "18") (name "Net-(DL4-RED_C)") (class "Default")
      (node (ref "DL4") (pin "5") (pinfunction "RED_C_5") (pintype "bidirectional"))
      (node (ref "R34") (pin "2") (pinfunction "2_2") (pintype "passive"))
    )
    (net (code "19") (name "Net-(F1-Pad1)") (class "Default")
      (node (ref "F1") (pin "1") (pinfunction "1_1") (pintype "passive"))
      (node (ref "J5") (pin "14") (pinfunction "14_14") (pintype "passive"))
    )
    (net (code "20") (name "Net-(F2-Pad1)") (class "Default")
      (node (ref "F2") (pin "1") (pinfunction "1_1") (pintype "passive"))
      (node (ref "J7") (pin "1") (pinfunction "1_1") (pintype "passive"))
    )
    (net (code "21") (name "Net-(J2-Pad3)") (class "Default")
      (node (ref "J2") (pin "3") (pinfunction "3_3") (pintype "passive"))
      (node (ref "R2") (pin "1") (pinfunction "1_1") (pintype "passive"))
    )
    (net (code "22") (name "Net-(J5-Pad6)") (class "Default")
      (node (ref "J5") (pin "6") (pinfunction "6_6") (pintype "passive"))
      (node (ref "R31") (pin "1") (pinfunction "1_1") (pintype "passive"))
    )
    (net (code "23") (name "Net-(J5-Pad7)") (class "Default")
      (node (ref "J5") (pin "7") (pinfunction "7_7") (pintype "passive"))
      (node (ref "R32") (pin "1") (pinfunction "1_1") (pintype "passive"))
    )
    (net (code "24") (name "Net-(JCLK-P$1)") (class "Default")
      (node (ref "JCLK") (pin "X") (pinfunction "P$1_X") (pintype "passive"))
      (node (ref "R18") (pin "1") (pinfunction "1_1") (pintype "passive"))
      (node (ref "U2") (pin "35") (pinfunction "JTCLK/GPIO13_35") (pintype "bidirectional"))
    )
    (net (code "25") (name "Net-(JTDO-P$1)") (class "Default")
      (node (ref "JTDO") (pin "X") (pinfunction "P$1_X") (pintype "passive"))
      (node (ref "R22") (pin "2") (pinfunction "2_2") (pintype "passive"))
      (node (ref "U2") (pin "32") (pinfunction "JTDO/GPIO15_32") (pintype "bidirectional"))
    )
    (net (code "26") (name "Net-(JTMS-P$1)") (class "Default")
      (node (ref "JTMS") (pin "X") (pinfunction "P$1_X") (pintype "passive"))
      (node (ref "R20") (pin "1") (pinfunction "1_1") (pintype "passive"))
      (node (ref "U2") (pin "31") (pinfunction "JTMS/GPIO14_31") (pintype "bidirectional"))
    )
    (net (code "27") (name "Net-(LPO_IN-P$1)") (class "Default")
      (node (ref "LPO_IN") (pin "X") (pinfunction "P$1_X") (pintype "passive"))
      (node (ref "U2") (pin "5") (pinfunction "LPO_IN/GPIO32_5") (pintype "bidirectional"))
    )
    (net (code "28") (name "Net-(PB1-2)") (class "Default")
      (node (ref "PB1") (pin "6") (pinfunction "2_6") (pintype "passive"))
      (node (ref "R3") (pin "1") (pinfunction "1_1") (pintype "passive"))
    )
    (net (code "29") (name "Net-(Q5A-D)") (class "Default")
      (node (ref "Q5") (pin "6") (pinfunction "D_6") (pintype "passive"))
      (node (ref "R7") (pin "1") (pinfunction "1_1") (pintype "passive"))
      (node (ref "RST") (pin "X") (pinfunction "P$1_X") (pintype "passive"))
      (node (ref "U2") (pin "19") (pinfunction "RESET_N_19") (pintype "bidirectional"))
    )
    (net (code "30") (name "Net-(Q5B-G)") (class "Default")
      (node (ref "Q5") (pin "5") (pinfunction "G_5") (pintype "passive"))
      (node (ref "R11") (pin "1") (pinfunction "1_1") (pintype "passive"))
      (node (ref "R17") (pin "2") (pinfunction "2_2") (pintype "passive"))
    )
    (net (code "31") (name "Net-(U1A-PB09)") (class "Default")
      (node (ref "C6") (pin "1") (pinfunction "1_1") (pintype "passive"))
      (node (ref "R8") (pin "1") (pinfunction "1_1") (pintype "passive"))
      (node (ref "R9") (pin "2") (pinfunction "2_2") (pintype "passive"))
      (node (ref "U1") (pin "8") (pinfunction "PB09_8") (pintype "bidirectional"))
    )
    (net (code "32") (name "Net-(U1B-VDDANA)") (class "Default")
      (node (ref "C23") (pin "1") (pinfunction "1_1") (pintype "passive"))
      (node (ref "C27") (pin "1") (pinfunction "1_1") (pintype "passive"))
      (node (ref "L3") (pin "2") (pinfunction "2_2") (pintype "passive"))
      (node (ref "U1") (pin "6") (pinfunction "VDDANA_6") (pintype "power_in"))
    )
    (net (code "33") (name "Net-(U1B-VDDCORE)") (class "Default")
      (node (ref "C25") (pin "1") (pinfunction "1_1") (pintype "passive"))
      (node (ref "U1") (pin "43") (pinfunction "VDDCORE_43") (pintype "power_in"))
    )
    (net (code "34") (name "Net-(U2A-RMII_MDIO{slash}GPIO4)") (class "Default")
      (node (ref "R17") (pin "1") (pinfunction "1_1") (pintype "passive"))
      (node (ref "U2") (pin "24") (pinfunction "RMII_MDIO/GPIO4_24") (pintype "bidirectional"))
    )
    (net (code "35") (name "Net-(U2A-SPIV_HD{slash}RMII_TXEN{slash}GPIO21)") (class "Default")
      (node (ref "R12") (pin "2") (pinfunction "2_2") (pintype "passive"))
      (node (ref "U2") (pin "8") (pinfunction "SPIV_HD/RMII_TXEN/GPIO21_8") (pintype "bidirectional"))
    )
    (net (code "36") (name "Net-(U5-BTST)") (class "Default")
      (node (ref "C15") (pin "1") (pinfunction "1_1") (pintype "passive"))
      (node (ref "U5") (pin "21") (pinfunction "BTST_21") (pintype "bidirectional"))
    )
    (net (code "37") (name "Net-(U5-CE)") (class "Default")
      (node (ref "R25") (pin "2") (pinfunction "2_2") (pintype "passive"))
      (node (ref "U5") (pin "9") (pinfunction "CE_9") (pintype "bidirectional"))
    )
    (net (code "38") (name "Net-(U5-ILIM)") (class "Default")
      (node (ref "R28") (pin "1") (pinfunction "1_1") (pintype "passive"))
      (node (ref "U5") (pin "10") (pinfunction "ILIM_10") (pintype "bidirectional"))
    )
    (net (code "39") (name "Net-(U5-INT)") (class "Default")
      (node (ref "R24") (pin "2") (pinfunction "2_2") (pintype "passive"))
      (node (ref "U5") (pin "7") (pinfunction "INT_7") (pintype "bidirectional"))
    )
    (net (code "40") (name "Net-(U5-OTG)") (class "Default")
      (node (ref "Q3") (pin "D") (pinfunction "D_D") (pintype "passive"))
      (node (ref "R26") (pin "2") (pinfunction "2_2") (pintype "passive"))
      (node (ref "U5") (pin "8") (pinfunction "OTG_8") (pintype "bidirectional"))
    )
    (net (code "41") (name "Net-(U5-PMID)") (class "Default")
      (node (ref "C12") (pin "1") (pinfunction "1_1") (pintype "passive"))
      (node (ref "C13") (pin "1") (pinfunction "1_1") (pintype "passive"))
      (node (ref "D3") (pin "A") (pinfunction "A_A") (pintype "passive"))
      (node (ref "U5") (pin "23") (pinfunction "PMID_23") (pintype "bidirectional"))
    )
    (net (code "42") (name "Net-(U5-REGN)") (class "Default")
      (node (ref "C16") (pin "1") (pinfunction "1_1") (pintype "passive"))
      (node (ref "R30") (pin "1") (pinfunction "1_1") (pintype "passive"))
      (node (ref "U5") (pin "22") (pinfunction "REGN_22") (pintype "bidirectional"))
    )
    (net (code "43") (name "Net-(U5-STAT)") (class "Default")
      (node (ref "DL2") (pin "C") (pinfunction "C_C") (pintype "passive"))
      (node (ref "U5") (pin "4") (pinfunction "STAT_4") (pintype "bidirectional"))
    )
    (net (code "44") (name "Net-(U5-TS1)") (class "Default")
      (node (ref "R29") (pin "2") (pinfunction "2_2") (pintype "passive"))
      (node (ref "R30") (pin "2") (pinfunction "2_2") (pintype "passive"))
      (node (ref "U5") (pin "11") (pinfunction "TS1_11") (pintype "bidirectional"))
      (node (ref "U5") (pin "12") (pinfunction "TS2_12") (pintype "bidirectional"))
    )
    (net (code "45") (name "PA00_XIN32") (class "Default")
      (node (ref "C3") (pin "2") (pinfunction "2_2") (pintype "passive"))
      (node (ref "U1") (pin "1") (pinfunction "PA00/XIN32_1") (pintype "bidirectional"))
      (node (ref "Y1") (pin "2") (pinfunction "2_2") (pintype "passive"))
    )
    (net (code "46") (name "PA01_XOUT32") (class "Default")
      (node (ref "C4") (pin "2") (pinfunction "2_2") (pintype "passive"))
      (node (ref "U1") (pin "2") (pinfunction "PA01/XOUT32_2") (pintype "bidirectional"))
      (node (ref "Y1") (pin "1") (pinfunction "1_1") (pintype "passive"))
    )
    (net (code "47") (name "PA02_AIN0") (class "Default")
      (node (ref "J3") (pin "2") (pinfunction "2_2") (pintype "passive"))
      (node (ref "U1") (pin "3") (pinfunction "PA02_3") (pintype "bidirectional"))
    )
    (net (code "48") (name "PA03_VREFA") (class "Default")
      (node (ref "C5") (pin "1") (pinfunction "1_1") (pintype "passive"))
      (node (ref "C7") (pin "1") (pinfunction "1_1") (pintype "passive"))
      (node (ref "J3") (pin "1") (pinfunction "1_1") (pintype "passive"))
      (node (ref "U1") (pin "4") (pinfunction "PA03_4") (pintype "bidirectional"))
    )
    (net (code "49") (name "PA04_AIN4") (class "Default")
      (node (ref "J3") (pin "5") (pinfunction "5_5") (pintype "passive"))
      (node (ref "U1") (pin "9") (pinfunction "PA04_9") (pintype "bidirectional"))
    )
    (net (code "50") (name "PA05_AIN5") (class "Default")
      (node (ref "J3") (pin "6") (pinfunction "6_6") (pintype "passive"))
      (node (ref "U1") (pin "10") (pinfunction "PA05_10") (pintype "bidirectional"))
    )
    (net (code "51") (name "PA06_AIN6") (class "Default")
      (node (ref "J3") (pin "7") (pinfunction "7_7") (pintype "passive"))
      (node (ref "U1") (pin "11") (pinfunction "PA06_11") (pintype "bidirectional"))
    )
    (net (code "52") (name "PA07_AIN7") (class "Default")
      (node (ref "J3") (pin "8") (pinfunction "8_8") (pintype "passive"))
      (node (ref "U1") (pin "12") (pinfunction "PA07_12") (pintype "bidirectional"))
    )
    (net (code "53") (name "PA08_S0_I2C_SDA") (class "Default")
      (node (ref "ESDA") (pin "X") (pinfunction "P$1_X") (pintype "passive"))
      (node (ref "J4") (pin "4") (pinfunction "4_4") (pintype "passive"))
      (node (ref "R14") (pin "1") (pinfunction "1_1") (pintype "passive"))
      (node (ref "R18") (pin "2") (pinfunction "2_2") (pintype "passive"))
      (node (ref "R31") (pin "2") (pinfunction "2_2") (pintype "passive"))
      (node (ref "U1") (pin "13") (pinfunction "PA08_13") (pintype "bidirectional"))
      (node (ref "U4") (pin "5") (pinfunction "SDA_5") (pintype "bidirectional"))
      (node (ref "U5") (pin "6") (pinfunction "SDA_6") (pintype "bidirectional"))
    )
    (net (code "54") (name "PA09_S0_I2C_SCL") (class "Default")
      (node (ref "ESCL") (pin "X") (pinfunction "P$1_X") (pintype "passive"))
      (node (ref "J4") (pin "3") (pinfunction "3_3") (pintype "passive"))
      (node (ref "R13") (pin "1") (pinfunction "1_1") (pintype "passive"))
      (node (ref "R20") (pin "2") (pinfunction "2_2") (pintype "passive"))
      (node (ref "R32") (pin "2") (pinfunction "2_2") (pintype "passive"))
      (node (ref "U1") (pin "14") (pinfunction "PA09_14") (pintype "bidirectional"))
      (node (ref "U4") (pin "6") (pinfunction "SCL_6") (pintype "input"))
      (node (ref "U5") (pin "5") (pinfunction "SCL_5") (pintype "bidirectional"))
    )
    (net (code "55") (name "PA10_TCC0-W2") (class "Default")
      (node (ref "J3") (pin "11") (pinfunction "11_11") (pintype "passive"))
      (node (ref "U1") (pin "15") (pinfunction "PA10_15") (pintype "bidirectional"))
    )
    (net (code "56") (name "PA11_TCC0-W3") (class "Default")
      (node (ref "J3") (pin "12") (pinfunction "12_12") (pintype "passive"))
      (node (ref "U1") (pin "16") (pinfunction "PA11_16") (pintype "bidirectional"))
    )
    (net (code "57") (name "PA12_S2_TX{slash}MOSI") (class "Default")
      (node (ref "U1") (pin "21") (pinfunction "PA12_21") (pintype "bidirectional"))
      (node (ref "U2") (pin "36") (pinfunction "GPIO12_36") (pintype "bidirectional"))
    )
    (net (code "58") (name "PA13_S2_RX{slash}MISO") (class "Default")
      (node (ref "U1") (pin "22") (pinfunction "PA13_22") (pintype "bidirectional"))
      (node (ref "U2") (pin "1") (pinfunction "SPIV_DI/GPIO23_1") (pintype "bidirectional"))
    )
    (net (code "59") (name "PA14_S2_RTS{slash}CS") (class "Default")
      (node (ref "U1") (pin "23") (pinfunction "PA14_23") (pintype "bidirectional"))
      (node (ref "U2") (pin "21") (pinfunction "UART_CTS/RMII_TXD0/SPIV_D0/GPIO19_21") (pintype "bidirectional"))
      (node (ref "U2") (pin "28") (pinfunction "SPIV_CS/GPIO5_28") (pintype "bidirectional"))
    )
    (net (code "60") (name "PA15_S2_CTS{slash}SCK") (class "Default")
      (node (ref "U1") (pin "24") (pinfunction "PA15_24") (pintype "bidirectional"))
      (node (ref "U2") (pin "20") (pinfunction "UART_RTS/RMII_TXD1/SPIV_WP/GPIO22_20") (pintype "bidirectional"))
      (node (ref "U2") (pin "29") (pinfunction "SPIV_CLK/GPIO18_29") (pintype "bidirectional"))
    )
    (net (code "61") (name "PA16_S1_MOSI") (class "Default")
      (node (ref "J5") (pin "3") (pinfunction "3_3") (pintype "passive"))
      (node (ref "U1") (pin "25") (pinfunction "PA16_25") (pintype "bidirectional"))
    )
    (net (code "62") (name "PA17_S1_SCK") (class "Default")
      (node (ref "J5") (pin "4") (pinfunction "4_4") (pintype "passive"))
      (node (ref "U1") (pin "26") (pinfunction "PA17_26") (pintype "bidirectional"))
    )
    (net (code "63") (name "PA18_OTG") (class "Default")
      (node (ref "J1") (pin "4") (pinfunction "4_4") (pintype "passive"))
      (node (ref "Q3") (pin "G") (pinfunction "G_G") (pintype "passive"))
      (node (ref "R21") (pin "2") (pinfunction "2_2") (pintype "passive"))
      (node (ref "U1") (pin "27") (pinfunction "PA18_27") (pintype "bidirectional"))
    )
    (net (code "64") (name "PA19_S1_MISO") (class "Default")
      (node (ref "J5") (pin "5") (pinfunction "5_5") (pintype "passive"))
      (node (ref "U1") (pin "28") (pinfunction "PA19_28") (pintype "bidirectional"))
    )
    (net (code "65") (name "PA20_TCC0-W6") (class "Default")
      (node (ref "J5") (pin "1") (pinfunction "1_1") (pintype "passive"))
      (node (ref "Q1") (pin "G") (pinfunction "G_G") (pintype "passive"))
      (node (ref "R16") (pin "2") (pinfunction "2_2") (pintype "passive"))
      (node (ref "U1") (pin "29") (pinfunction "PA20_29") (pintype "bidirectional"))
    )
    (net (code "66") (name "PA21_TCC0-W7") (class "Default")
      (node (ref "EWK") (pin "X") (pinfunction "P$1_X") (pintype "passive"))
      (node (ref "J4") (pin "2") (pinfunction "2_2") (pintype "passive"))
      (node (ref "J5") (pin "2") (pinfunction "2_2") (pintype "passive"))
      (node (ref "U1") (pin "30") (pinfunction "PA21_30") (pintype "bidirectional"))
    )
    (net (code "67") (name "PA22_TC4-W0") (class "Default")
      (node (ref "J3") (pin "9") (pinfunction "9_9") (pintype "passive"))
      (node (ref "U1") (pin "31") (pinfunction "PA22_31") (pintype "bidirectional"))
    )
    (net (code "68") (name "PA23_TC4-W1") (class "Default")
      (node (ref "J3") (pin "10") (pinfunction "10_10") (pintype "passive"))
      (node (ref "U1") (pin "32") (pinfunction "PA23_32") (pintype "bidirectional"))
    )
    (net (code "69") (name "PA27_GPIO0") (class "Default")
      (node (ref "GPIO0") (pin "X") (pinfunction "P$1_X") (pintype "passive"))
      (node (ref "U1") (pin "39") (pinfunction "PA27_39") (pintype "bidirectional"))
      (node (ref "U2") (pin "27") (pinfunction "RMII_CLK/GPIO0_27") (pintype "bidirectional"))
    )
    (net (code "70") (name "PA28_ACK") (class "Default")
      (node (ref "U1") (pin "41") (pinfunction "PA28_41") (pintype "bidirectional"))
      (node (ref "U2") (pin "7") (pinfunction "GPIO33_7") (pintype "bidirectional"))
    )
    (net (code "71") (name "PA30_SWCLK") (class "Default")
      (node (ref "J2") (pin "4") (pinfunction "4_4") (pintype "passive"))
      (node (ref "R12") (pin "1") (pinfunction "1_1") (pintype "passive"))
      (node (ref "R4") (pin "1") (pinfunction "1_1") (pintype "passive"))
      (node (ref "U1") (pin "45") (pinfunction "PA30/SWCLK_45") (pintype "bidirectional"))
    )
    (net (code "72") (name "PA31_SWDIO") (class "Default")
      (node (ref "J2") (pin "2") (pinfunction "2_2") (pintype "passive"))
      (node (ref "R22") (pin "1") (pinfunction "1_1") (pintype "passive"))
      (node (ref "U1") (pin "46") (pinfunction "PA31/SWDIO_46") (pintype "bidirectional"))
    )
    (net (code "73") (name "PB02_AIN10") (class "Default")
      (node (ref "J3") (pin "3") (pinfunction "3_3") (pintype "passive"))
      (node (ref "U1") (pin "47") (pinfunction "PB02_47") (pintype "bidirectional"))
    )
    (net (code "74") (name "PB03_AIN11") (class "Default")
      (node (ref "J3") (pin "4") (pinfunction "4_4") (pintype "passive"))
      (node (ref "U1") (pin "48") (pinfunction "PB03_48") (pintype "bidirectional"))
    )
    (net (code "75") (name "PB08_RST") (class "Default")
      (node (ref "Q5") (pin "2") (pinfunction "G_2") (pintype "passive"))
      (node (ref "R10") (pin "1") (pinfunction "1_1") (pintype "passive"))
      (node (ref "U1") (pin "7") (pinfunction "PB08_7") (pintype "bidirectional"))
    )
    (net (code "76") (name "PB10_TCC0-W4") (class "Default")
      (node (ref "J3") (pin "13") (pinfunction "13_13") (pintype "passive"))
      (node (ref "U1") (pin "19") (pinfunction "PB10_19") (pintype "bidirectional"))
    )
    (net (code "77") (name "PB11_TCC0-W5") (class "Default")
      (node (ref "J3") (pin "14") (pinfunction "14_14") (pintype "passive"))
      (node (ref "U1") (pin "20") (pinfunction "PB11_20") (pintype "bidirectional"))
    )
    (net (code "78") (name "PB22_S5_TX") (class "Default")
      (node (ref "J5") (pin "9") (pinfunction "9_9") (pintype "passive"))
      (node (ref "RXD") (pin "X") (pinfunction "P$1_X") (pintype "passive"))
      (node (ref "U1") (pin "37") (pinfunction "PB22_37") (pintype "bidirectional"))
      (node (ref "U2") (pin "23") (pinfunction "UART_RXD/GPIO3_23") (pintype "bidirectional"))
    )
    (net (code "79") (name "PB23_S5_RX") (class "Default")
      (node (ref "J5") (pin "8") (pinfunction "8_8") (pintype "passive"))
      (node (ref "TXD") (pin "X") (pinfunction "P$1_X") (pintype "passive"))
      (node (ref "U1") (pin "38") (pinfunction "PB23_38") (pintype "bidirectional"))
      (node (ref "U2") (pin "22") (pinfunction "UART_TXD/GPIO1_22") (pintype "bidirectional"))
    )
    (net (code "80") (name "RESET#") (class "Default")
      (node (ref "J5") (pin "10") (pinfunction "10_10") (pintype "passive"))
      (node (ref "Q5") (pin "3") (pinfunction "D_3") (pintype "passive"))
      (node (ref "R6") (pin "2") (pinfunction "2_2") (pintype "passive"))
    )
    (net (code "81") (name "RESETN") (class "Default")
      (node (ref "C2") (pin "1") (pinfunction "1_1") (pintype "passive"))
      (node (ref "R2") (pin "2") (pinfunction "2_2") (pintype "passive"))
      (node (ref "R3") (pin "2") (pinfunction "2_2") (pintype "passive"))
      (node (ref "R5") (pin "1") (pinfunction "1_1") (pintype "passive"))
      (node (ref "R6") (pin "1") (pinfunction "1_1") (pintype "passive"))
      (node (ref "U1") (pin "40") (pinfunction "RESETN_40") (pintype "bidirectional"))
    )
    (net (code "82") (name "USB_N") (class "Default")
      (node (ref "D-") (pin "X") (pinfunction "P$1_X") (pintype "passive"))
      (node (ref "D1") (pin "3") (pinfunction "3_3") (pintype "passive"))
      (node (ref "J1") (pin "2") (pinfunction "2_2") (pintype "passive"))
      (node (ref "U1") (pin "33") (pinfunction "PA24/USB_DM_33") (pintype "bidirectional"))
    )
    (net (code "83") (name "USB_P") (class "Default")
      (node (ref "D+") (pin "X") (pinfunction "P$1_X") (pintype "passive"))
      (node (ref "D1") (pin "2") (pinfunction "2_2") (pintype "passive"))
      (node (ref "J1") (pin "3") (pinfunction "3_3") (pintype "passive"))
      (node (ref "U1") (pin "34") (pinfunction "PA25/USB_DP_34") (pintype "bidirectional"))
    )
    (net (code "84") (name "VBATT") (class "Default")
      (node (ref "BATT+") (pin "X") (pinfunction "P$1_X") (pintype "passive"))
      (node (ref "D2") (pin "C") (pinfunction "C_C") (pintype "passive"))
      (node (ref "F2") (pin "2") (pinfunction "2_2") (pintype "passive"))
      (node (ref "R8") (pin "2") (pinfunction "2_2") (pintype "passive"))
      (node (ref "U5") (pin "13") (pinfunction "BAT_13") (pintype "bidirectional"))
      (node (ref "U5") (pin "14") (pinfunction "BAT_14") (pintype "bidirectional"))
    )
    (net (code "85") (name "VIN") (class "Default")
      (node (ref "J5") (pin "13") (pinfunction "13_13") (pintype "passive"))
      (node (ref "Q2") (pin "A") (pinfunction "A_A") (pintype "passive"))
      (node (ref "Q2") (pin "G") (pinfunction "G_G") (pintype "passive"))
      (node (ref "R19") (pin "2") (pinfunction "2_2") (pintype "passive"))
    )
    (net (code "86") (name "unconnected-(J2-Pad6)") (class "Default")
      (node (ref "J2") (pin "6") (pinfunction "6_6") (pintype "passive"))
    )
    (net (code "87") (name "unconnected-(U2A-ADC2{slash}GPIO34-Pad2)") (class "Default")
      (node (ref "U2") (pin "2") (pinfunction "ADC2/GPIO34_2") (pintype "bidirectional"))
    )
    (net (code "88") (name "unconnected-(U2A-ADC3{slash}GPIO39-Pad3)") (class "Default")
      (node (ref "U2") (pin "3") (pinfunction "ADC3/GPIO39_3") (pintype "bidirectional"))
    )
    (net (code "89") (name "unconnected-(U2A-ADC4{slash}GPIO36-Pad4)") (class "Default")
      (node (ref "U2") (pin "4") (pinfunction "ADC4/GPIO36_4") (pintype "bidirectional"))
    )
    (net (code "90") (name "unconnected-(U2A-ADC34{slash}GPI35-Pad34)") (class "Default")
      (node (ref "U2") (pin "34") (pinfunction "ADC34/GPI35_34") (pintype "bidirectional"))
    )
    (net (code "91") (name "unconnected-(U2A-ANT-Pad13)") (class "Default")
      (node (ref "U2") (pin "13") (pinfunction "ANT_13") (pintype "bidirectional"))
    )
    (net (code "92") (name "unconnected-(U2A-RMII_MDCLK{slash}GPIO2-Pad25)") (class "Default")
      (node (ref "U2") (pin "25") (pinfunction "RMII_MDCLK/GPIO2_25") (pintype "bidirectional"))
    )
    (net (code "93") (name "unconnected-(U4B-EP-Pad9)") (class "Default")
      (node (ref "U4") (pin "9") (pinfunction "EP_9") (pintype "passive"))
    )
    (net (code "94") (name "unconnected-(U4B-NC-Pad1)") (class "Default")
      (node (ref "U4") (pin "1") (pinfunction "NC_1") (pintype "bidirectional"))
    )
    (net (code "95") (name "unconnected-(U4B-NC-Pad2)") (class "Default")
      (node (ref "U4") (pin "2") (pinfunction "NC_2") (pintype "bidirectional"))
    )
    (net (code "96") (name "unconnected-(U4B-NC-Pad3)") (class "Default")
      (node (ref "U4") (pin "3") (pinfunction "NC_3") (pintype "bidirectional"))
    )
    (net (code "97") (name "unconnected-(U4B-NC-Pad7)") (class "Default")
      (node (ref "U4") (pin "7") (pinfunction "NC_7") (pintype "bidirectional"))
    )
    (net (code "98") (name "unconnected-(U5-D+-Pad2)") (class "Default")
      (node (ref "U5") (pin "2") (pinfunction "D+_2") (pintype "bidirectional"))
    )
    (net (code "99") (name "unconnected-(U5-D--Pad3)") (class "Default")
      (node (ref "U5") (pin "3") (pinfunction "D-_3") (pintype "bidirectional"))
    )
  )
)
